# satshakit128.net
KiCad netlist of a schematic drawn in EAGLE
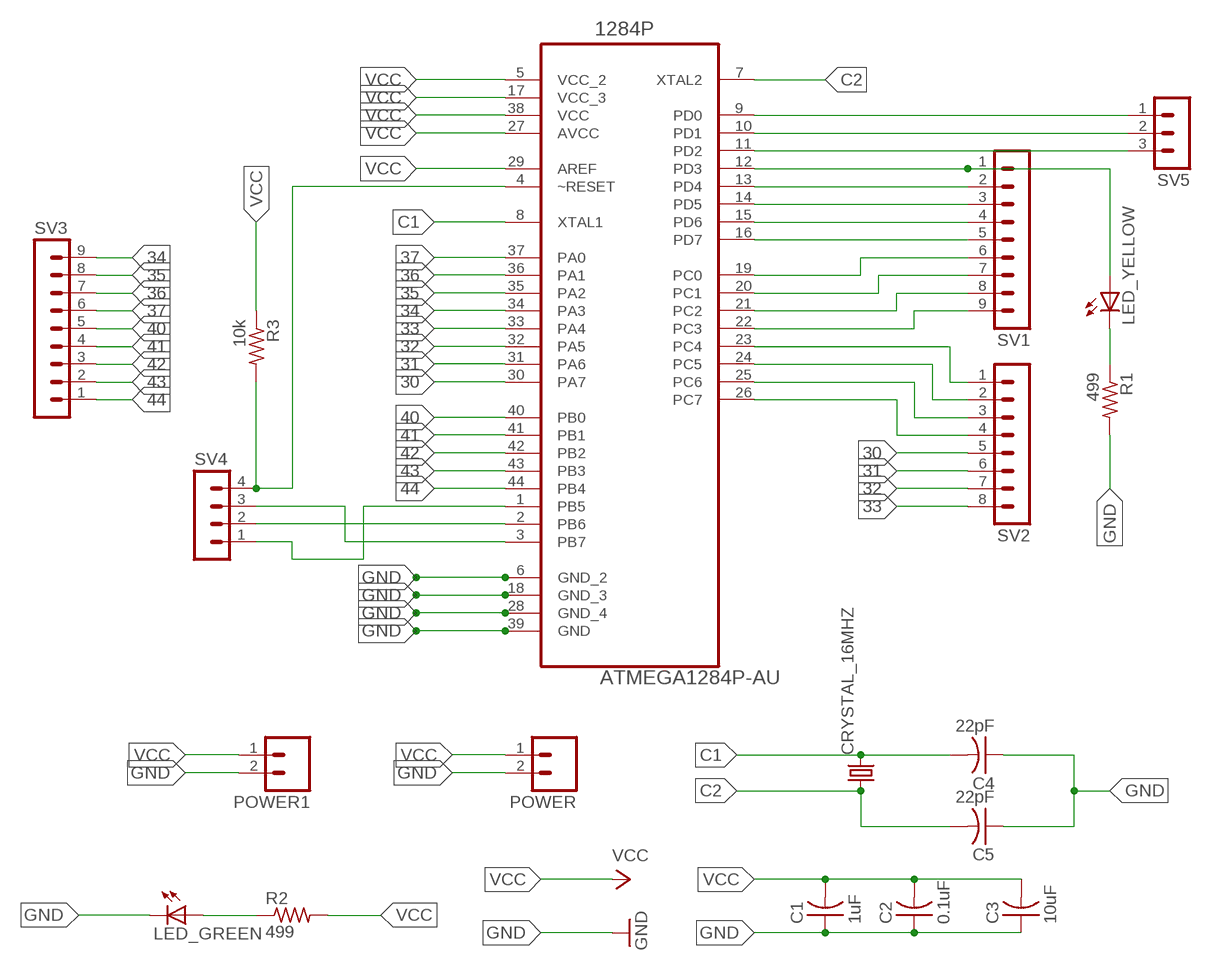
[diagram p0: schematic, sheet 1]

(export (version "E")
  (design (tool "Eeschema 10.0.6"))
  (components
    (comp (ref "1284P")
      (value "ATMEGA1284P-AU")
      (footprint "eagle-import:QFP80P1200X1200X120-44N")
      (libsource (lib "eagle-import") (part "ATMEGA1284P-AU"))
    )
    (comp (ref "C1")
      (value "1uF")
      (footprint "eagle-import:C1206")
      (libsource (lib "eagle-import") (part "CAP-US1206"))
    )
    (comp (ref "C2")
      (value "0.1uF")
      (footprint "eagle-import:C1206")
      (libsource (lib "eagle-import") (part "CAP-US1206"))
    )
    (comp (ref "C3")
      (value "10uF")
      (footprint "eagle-import:C1206")
      (libsource (lib "eagle-import") (part "CAP-US1206"))
    )
    (comp (ref "C4")
      (value "22pF")
      (footprint "eagle-import:C1206")
      (libsource (lib "eagle-import") (part "CAP-US1206"))
    )
    (comp (ref "C5")
      (value "22pF")
      (footprint "eagle-import:C1206")
      (libsource (lib "eagle-import") (part "CAP-US1206"))
    )
    (comp (ref "CRYSTAL_16MHZ")
      (value "CRYSTALHC49UP")
      (footprint "eagle-import:HC49UP")
      (libsource (lib "eagle-import") (part "CRYSTALHC49UP"))
    )
    (comp (ref "LED_GREEN")
      (value "LED1206")
      (footprint "eagle-import:1206")
      (libsource (lib "eagle-import") (part "LED1206"))
    )
    (comp (ref "LED_YELLOW")
      (value "LED1206")
      (footprint "eagle-import:1206")
      (libsource (lib "eagle-import") (part "LED1206"))
    )
    (comp (ref "POWER")
      (value "M02")
      (footprint "eagle-import:02P")
      (libsource (lib "eagle-import") (part "M02"))
    )
    (comp (ref "POWER1")
      (value "M02")
      (footprint "eagle-import:02P")
      (libsource (lib "eagle-import") (part "M02"))
    )
    (comp (ref "R1")
      (value "499")
      (footprint "eagle-import:R1206")
      (libsource (lib "eagle-import") (part "RES-US1206"))
    )
    (comp (ref "R2")
      (value "499")
      (footprint "eagle-import:R1206")
      (libsource (lib "eagle-import") (part "RES-US1206"))
    )
    (comp (ref "R3")
      (value "10k")
      (footprint "eagle-import:R1206")
      (libsource (lib "eagle-import") (part "RES-US1206"))
    )
    (comp (ref "SV1")
      (value "MA09-1")
      (footprint "eagle-import:MA09-1")
      (libsource (lib "eagle-import") (part "MA09-1"))
    )
    (comp (ref "SV2")
      (value "MA08-1")
      (footprint "eagle-import:MA08-1")
      (libsource (lib "eagle-import") (part "MA08-1"))
    )
    (comp (ref "SV3")
      (value "MA09-1")
      (footprint "eagle-import:MA09-1")
      (libsource (lib "eagle-import") (part "MA09-1"))
    )
    (comp (ref "SV4")
      (value "MA04-1")
      (footprint "eagle-import:MA04-1")
      (libsource (lib "eagle-import") (part "MA04-1"))
    )
    (comp (ref "SV5")
      (value "MA03-1")
      (footprint "eagle-import:MA03-1")
      (libsource (lib "eagle-import") (part "MA03-1"))
    )
  )
  (nets
    (net (code "1") (name "30") (class "Default")
      (node (ref "1284P") (pin "30") (pinfunction "PA7_30") (pintype "bidirectional"))
      (node (ref "SV2") (pin "5") (pinfunction "5_5") (pintype "passive"))
    )
    (net (code "2") (name "31") (class "Default")
      (node (ref "1284P") (pin "31") (pinfunction "PA6_31") (pintype "bidirectional"))
      (node (ref "SV2") (pin "6") (pinfunction "6_6") (pintype "passive"))
    )
    (net (code "3") (name "32") (class "Default")
      (node (ref "1284P") (pin "32") (pinfunction "PA5_32") (pintype "bidirectional"))
      (node (ref "SV2") (pin "7") (pinfunction "7_7") (pintype "passive"))
    )
    (net (code "4") (name "33") (class "Default")
      (node (ref "1284P") (pin "33") (pinfunction "PA4_33") (pintype "bidirectional"))
      (node (ref "SV2") (pin "8") (pinfunction "8_8") (pintype "passive"))
    )
    (net (code "5") (name "34") (class "Default")
      (node (ref "1284P") (pin "34") (pinfunction "PA3_34") (pintype "bidirectional"))
      (node (ref "SV3") (pin "9") (pinfunction "9_9") (pintype "passive"))
    )
    (net (code "6") (name "35") (class "Default")
      (node (ref "1284P") (pin "35") (pinfunction "PA2_35") (pintype "bidirectional"))
      (node (ref "SV3") (pin "8") (pinfunction "8_8") (pintype "passive"))
    )
    (net (code "7") (name "36") (class "Default")
      (node (ref "1284P") (pin "36") (pinfunction "PA1_36") (pintype "bidirectional"))
      (node (ref "SV3") (pin "7") (pinfunction "7_7") (pintype "passive"))
    )
    (net (code "8") (name "37") (class "Default")
      (node (ref "1284P") (pin "37") (pinfunction "PA0_37") (pintype "bidirectional"))
      (node (ref "SV3") (pin "6") (pinfunction "6_6") (pintype "passive"))
    )
    (net (code "9") (name "40") (class "Default")
      (node (ref "1284P") (pin "40") (pinfunction "PB0_40") (pintype "bidirectional"))
      (node (ref "SV3") (pin "5") (pinfunction "5_5") (pintype "passive"))
    )
    (net (code "10") (name "41") (class "Default")
      (node (ref "1284P") (pin "41") (pinfunction "PB1_41") (pintype "bidirectional"))
      (node (ref "SV3") (pin "4") (pinfunction "4_4") (pintype "passive"))
    )
    (net (code "11") (name "42") (class "Default")
      (node (ref "1284P") (pin "42") (pinfunction "PB2_42") (pintype "bidirectional"))
      (node (ref "SV3") (pin "3") (pinfunction "3_3") (pintype "passive"))
    )
    (net (code "12") (name "43") (class "Default")
      (node (ref "1284P") (pin "43") (pinfunction "PB3_43") (pintype "bidirectional"))
      (node (ref "SV3") (pin "2") (pinfunction "2_2") (pintype "passive"))
    )
    (net (code "13") (name "44") (class "Default")
      (node (ref "1284P") (pin "44") (pinfunction "PB4_44") (pintype "bidirectional"))
      (node (ref "SV3") (pin "1") (pinfunction "1_1") (pintype "passive"))
    )
    (net (code "14") (name "C1") (class "Default")
      (node (ref "1284P") (pin "8") (pinfunction "XTAL1_8") (pintype "input"))
      (node (ref "C4") (pin "2") (pinfunction "2_2") (pintype "passive"))
      (node (ref "CRYSTAL_16MHZ") (pin "2") (pinfunction "2_2") (pintype "passive"))
    )
    (net (code "15") (name "C2") (class "Default")
      (node (ref "1284P") (pin "7") (pinfunction "XTAL2_7") (pintype "output"))
      (node (ref "C5") (pin "2") (pinfunction "2_2") (pintype "passive"))
      (node (ref "CRYSTAL_16MHZ") (pin "1") (pinfunction "1_1") (pintype "passive"))
    )
    (net (code "16") (name "GND") (class "Default")
      (node (ref "1284P") (pin "6") (pinfunction "GND_2_6") (pintype "passive"))
      (node (ref "C1") (pin "1") (pinfunction "1_1") (pintype "passive"))
      (node (ref "C2") (pin "1") (pinfunction "1_1") (pintype "passive"))
      (node (ref "C3") (pin "1") (pinfunction "1_1") (pintype "passive"))
      (node (ref "C4") (pin "1") (pinfunction "1_1") (pintype "passive"))
      (node (ref "C5") (pin "1") (pinfunction "1_1") (pintype "passive"))
      (node (ref "LED_GREEN") (pin "2") (pinfunction "C_2") (pintype "passive"))
      (node (ref "POWER") (pin "2") (pinfunction "2_2") (pintype "passive"))
      (node (ref "POWER1") (pin "2") (pinfunction "2_2") (pintype "passive"))
      (node (ref "R1") (pin "2") (pinfunction "2_2") (pintype "passive"))
    )
    (net (code "17") (name "Net-(1284P-PB5)") (class "Default")
      (node (ref "1284P") (pin "1") (pinfunction "PB5_1") (pintype "bidirectional"))
      (node (ref "SV4") (pin "1") (pinfunction "1_1") (pintype "passive"))
    )
    (net (code "18") (name "Net-(1284P-PB6)") (class "Default")
      (node (ref "1284P") (pin "2") (pinfunction "PB6_2") (pintype "bidirectional"))
      (node (ref "SV4") (pin "2") (pinfunction "2_2") (pintype "passive"))
    )
    (net (code "19") (name "Net-(1284P-PB7)") (class "Default")
      (node (ref "1284P") (pin "3") (pinfunction "PB7_3") (pintype "bidirectional"))
      (node (ref "SV4") (pin "3") (pinfunction "3_3") (pintype "passive"))
    )
    (net (code "20") (name "Net-(1284P-PC0)") (class "Default")
      (node (ref "1284P") (pin "19") (pinfunction "PC0_19") (pintype "bidirectional"))
      (node (ref "SV1") (pin "6") (pinfunction "6_6") (pintype "passive"))
    )
    (net (code "21") (name "Net-(1284P-PC1)") (class "Default")
      (node (ref "1284P") (pin "20") (pinfunction "PC1_20") (pintype "bidirectional"))
      (node (ref "SV1") (pin "7") (pinfunction "7_7") (pintype "passive"))
    )
    (net (code "22") (name "Net-(1284P-PC2)") (class "Default")
      (node (ref "1284P") (pin "21") (pinfunction "PC2_21") (pintype "bidirectional"))
      (node (ref "SV1") (pin "8") (pinfunction "8_8") (pintype "passive"))
    )
    (net (code "23") (name "Net-(1284P-PC3)") (class "Default")
      (node (ref "1284P") (pin "22") (pinfunction "PC3_22") (pintype "bidirectional"))
      (node (ref "SV1") (pin "9") (pinfunction "9_9") (pintype "passive"))
    )
    (net (code "24") (name "Net-(1284P-PC4)") (class "Default")
      (node (ref "1284P") (pin "23") (pinfunction "PC4_23") (pintype "bidirectional"))
      (node (ref "SV2") (pin "1") (pinfunction "1_1") (pintype "passive"))
    )
    (net (code "25") (name "Net-(1284P-PC5)") (class "Default")
      (node (ref "1284P") (pin "24") (pinfunction "PC5_24") (pintype "bidirectional"))
      (node (ref "SV2") (pin "2") (pinfunction "2_2") (pintype "passive"))
    )
    (net (code "26") (name "Net-(1284P-PC6)") (class "Default")
      (node (ref "1284P") (pin "25") (pinfunction "PC6_25") (pintype "bidirectional"))
      (node (ref "SV2") (pin "3") (pinfunction "3_3") (pintype "passive"))
    )
    (net (code "27") (name "Net-(1284P-PC7)") (class "Default")
      (node (ref "1284P") (pin "26") (pinfunction "PC7_26") (pintype "bidirectional"))
      (node (ref "SV2") (pin "4") (pinfunction "4_4") (pintype "passive"))
    )
    (net (code "28") (name "Net-(1284P-PD0)") (class "Default")
      (node (ref "1284P") (pin "9") (pinfunction "PD0_9") (pintype "bidirectional"))
      (node (ref "SV5") (pin "1") (pinfunction "1_1") (pintype "passive"))
    )
    (net (code "29") (name "Net-(1284P-PD1)") (class "Default")
      (node (ref "1284P") (pin "10") (pinfunction "PD1_10") (pintype "bidirectional"))
      (node (ref "SV5") (pin "2") (pinfunction "2_2") (pintype "passive"))
    )
    (net (code "30") (name "Net-(1284P-PD2)") (class "Default")
      (node (ref "1284P") (pin "11") (pinfunction "PD2_11") (pintype "bidirectional"))
      (node (ref "SV5") (pin "3") (pinfunction "3_3") (pintype "passive"))
    )
    (net (code "31") (name "Net-(1284P-PD3)") (class "Default")
      (node (ref "1284P") (pin "12") (pinfunction "PD3_12") (pintype "bidirectional"))
      (node (ref "LED_YELLOW") (pin "1") (pinfunction "A_1") (pintype "passive"))
      (node (ref "SV1") (pin "1") (pinfunction "1_1") (pintype "passive"))
    )
    (net (code "32") (name "Net-(1284P-PD4)") (class "Default")
      (node (ref "1284P") (pin "13") (pinfunction "PD4_13") (pintype "bidirectional"))
      (node (ref "SV1") (pin "2") (pinfunction "2_2") (pintype "passive"))
    )
    (net (code "33") (name "Net-(1284P-PD5)") (class "Default")
      (node (ref "1284P") (pin "14") (pinfunction "PD5_14") (pintype "bidirectional"))
      (node (ref "SV1") (pin "3") (pinfunction "3_3") (pintype "passive"))
    )
    (net (code "34") (name "Net-(1284P-PD6)") (class "Default")
      (node (ref "1284P") (pin "15") (pinfunction "PD6_15") (pintype "bidirectional"))
      (node (ref "SV1") (pin "4") (pinfunction "4_4") (pintype "passive"))
    )
    (net (code "35") (name "Net-(1284P-PD7)") (class "Default")
      (node (ref "1284P") (pin "16") (pinfunction "PD7_16") (pintype "bidirectional"))
      (node (ref "SV1") (pin "5") (pinfunction "5_5") (pintype "passive"))
    )
    (net (code "36") (name "Net-(1284P-~{RESET})") (class "Default")
      (node (ref "1284P") (pin "4") (pinfunction "~{RESET}_4") (pintype "input"))
      (node (ref "R3") (pin "2") (pinfunction "2_2") (pintype "passive"))
      (node (ref "SV4") (pin "4") (pinfunction "4_4") (pintype "passive"))
    )
    (net (code "37") (name "Net-(LED_GREEN-A)") (class "Default")
      (node (ref "LED_GREEN") (pin "1") (pinfunction "A_1") (pintype "passive"))
      (node (ref "R2") (pin "1") (pinfunction "1_1") (pintype "passive"))
    )
    (net (code "38") (name "Net-(LED_YELLOW-C)") (class "Default")
      (node (ref "LED_YELLOW") (pin "2") (pinfunction "C_2") (pintype "passive"))
      (node (ref "R1") (pin "1") (pinfunction "1_1") (pintype "passive"))
    )
    (net (code "39") (name "VCC") (class "Default")
      (node (ref "1284P") (pin "17") (pinfunction "VCC_3_17") (pintype "power_in"))
      (node (ref "1284P") (pin "27") (pinfunction "AVCC_27") (pintype "power_in"))
      (node (ref "1284P") (pin "29") (pinfunction "AREF_29") (pintype "input"))
      (node (ref "1284P") (pin "5") (pinfunction "VCC_2_5") (pintype "power_in"))
      (node (ref "C1") (pin "2") (pinfunction "2_2") (pintype "passive"))
      (node (ref "C2") (pin "2") (pinfunction "2_2") (pintype "passive"))
      (node (ref "C3") (pin "2") (pinfunction "2_2") (pintype "passive"))
      (node (ref "POWER") (pin "1") (pinfunction "1_1") (pintype "passive"))
      (node (ref "POWER1") (pin "1") (pinfunction "1_1") (pintype "passive"))
      (node (ref "R2") (pin "2") (pinfunction "2_2") (pintype "passive"))
      (node (ref "R3") (pin "1") (pinfunction "1_1") (pintype "passive"))
    )
    (net (code "40") (name "unconnected-(1284P-GND-Pad39)") (class "Default")
      (node (ref "1284P") (pin "39") (pinfunction "GND_39") (pintype "passive"))
    )
    (net (code "41") (name "unconnected-(1284P-GND_3-Pad18)") (class "Default")
      (node (ref "1284P") (pin "18") (pinfunction "GND_3_18") (pintype "passive"))
    )
    (net (code "42") (name "unconnected-(1284P-GND_4-Pad28)") (class "Default")
      (node (ref "1284P") (pin "28") (pinfunction "GND_4_28") (pintype "passive"))
    )
    (net (code "43") (name "unconnected-(1284P-VCC-Pad38)") (class "Default")
      (node (ref "1284P") (pin "38") (pinfunction "VCC_38") (pintype "power_in"))
    )
  )
)
